# interface_dac_sma_feedback_3PS_LM317.net
KiCad netlist of a schematic drawn in EAGLE
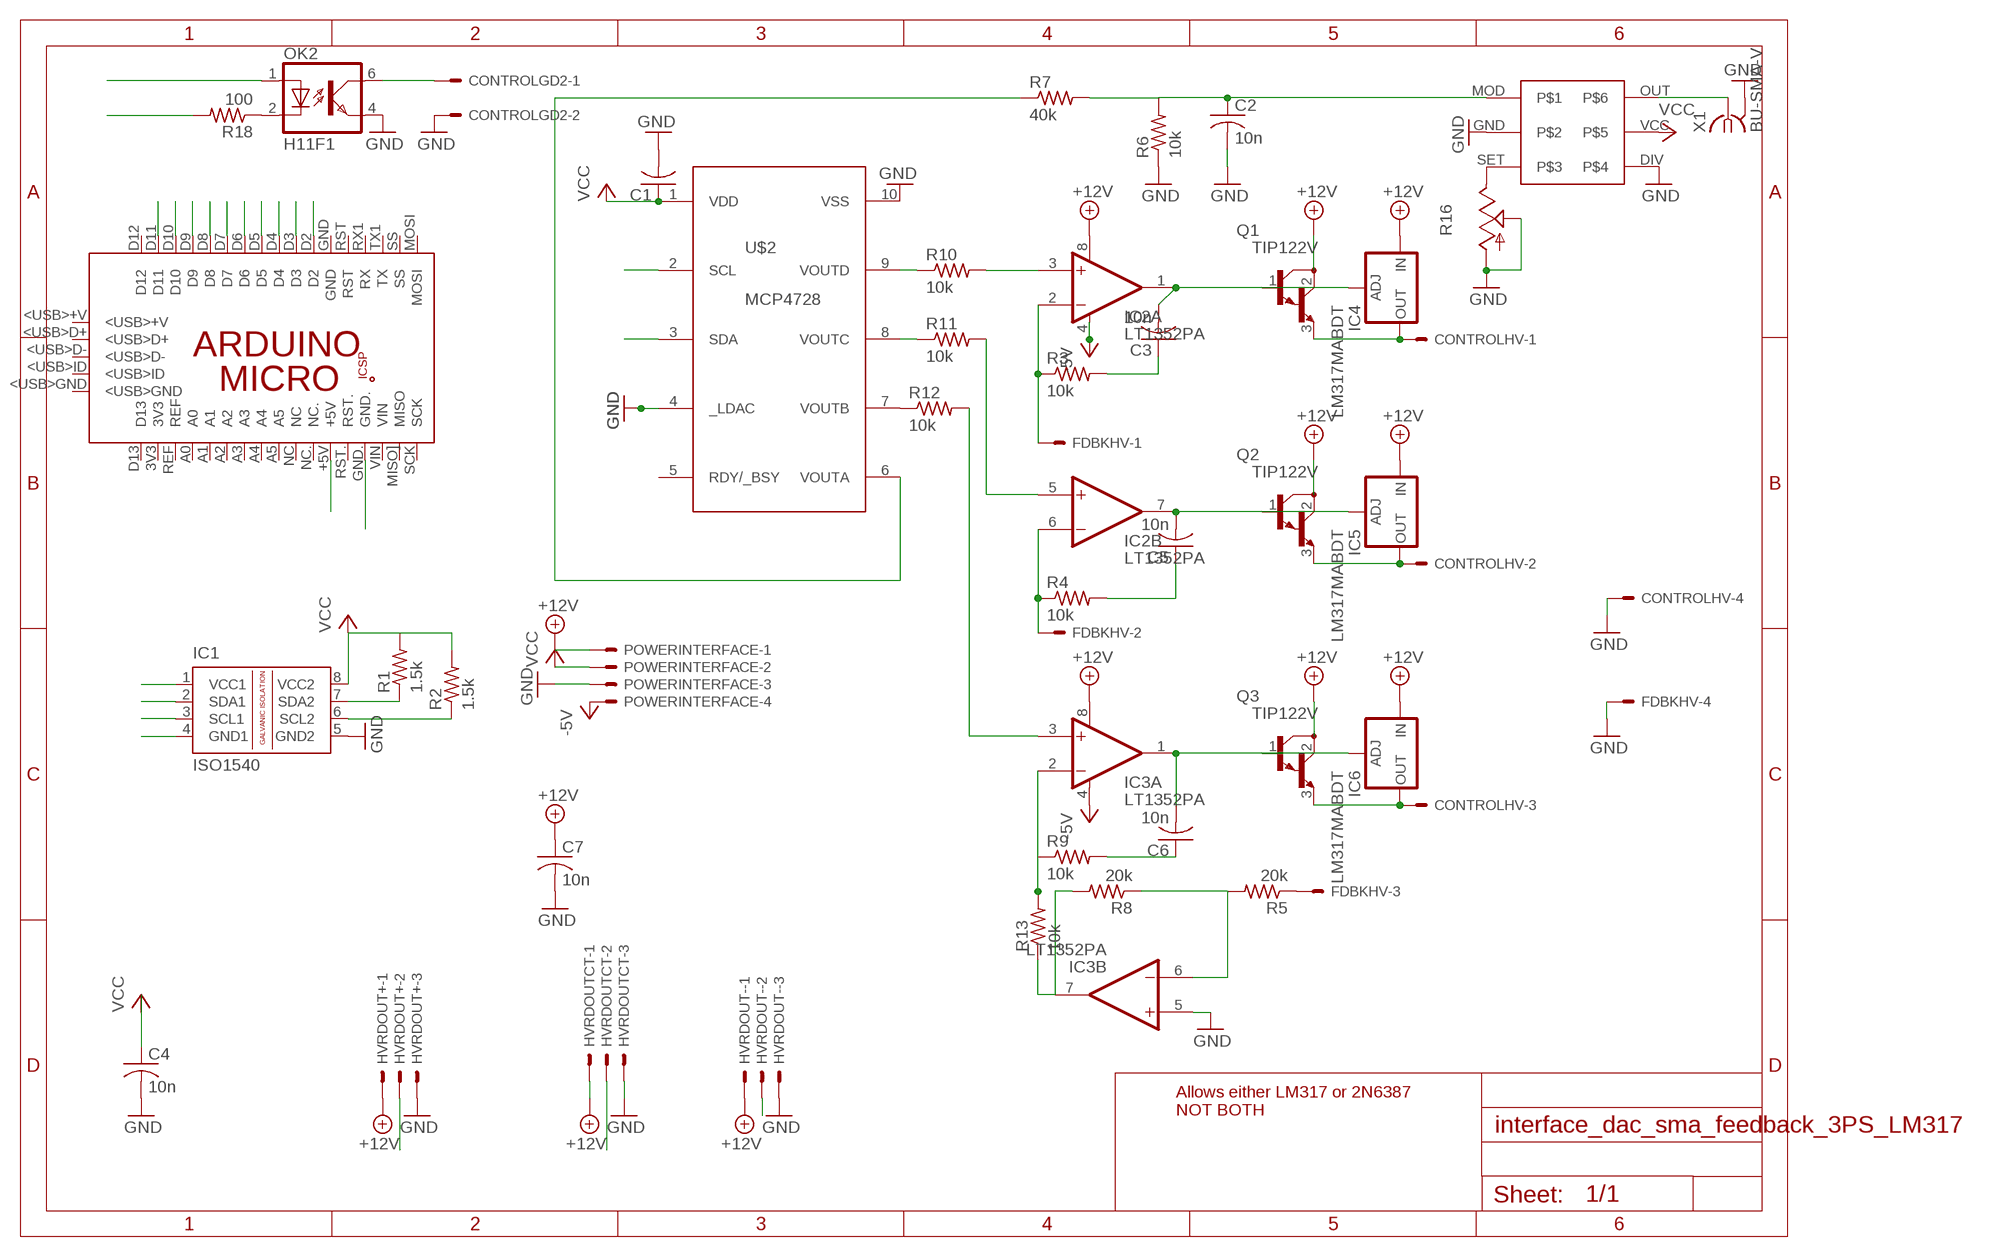
[diagram p0: schematic, sheet 1]

(export (version "E")
  (design (tool "Eeschema 10.0.6"))
  (components
    (comp (ref "C1")
      (value "C-US050-050X075")
      (footprint "eagle-import:C050-050X075")
      (libsource (lib "eagle-import") (part "C-US050-050X075"))
    )
    (comp (ref "C2")
      (value "10n")
      (footprint "eagle-import:C050-024X044")
      (libsource (lib "eagle-import") (part "resistor_C-US050-024X044"))
    )
    (comp (ref "C3")
      (value "10n")
      (footprint "eagle-import:C050-024X044")
      (libsource (lib "eagle-import") (part "resistor_C-US050-024X044"))
    )
    (comp (ref "C4")
      (value "10n")
      (footprint "eagle-import:C075-063X106")
      (libsource (lib "eagle-import") (part "resistor_C-US075-063X106"))
    )
    (comp (ref "C5")
      (value "10n")
      (footprint "eagle-import:C050-024X044")
      (libsource (lib "eagle-import") (part "resistor_C-US050-024X044"))
    )
    (comp (ref "C6")
      (value "10n")
      (footprint "eagle-import:C050-024X044")
      (libsource (lib "eagle-import") (part "resistor_C-US050-024X044"))
    )
    (comp (ref "C7")
      (value "10n")
      (footprint "eagle-import:C050-050X075")
      (libsource (lib "eagle-import") (part "resistor_C-US050-050X075"))
    )
    (comp (ref "CONTROLGD2")
      (value "KK-156-2")
      (footprint "eagle-import:KK-156-2")
      (libsource (lib "eagle-import") (part "KK-156-2"))
    )
    (comp (ref "CONTROLHV")
      (value "KK-156-4")
      (footprint "eagle-import:KK-156-4")
      (libsource (lib "eagle-import") (part "KK-156-4"))
    )
    (comp (ref "FDBKHV")
      (value "KK-156-4")
      (footprint "eagle-import:KK-156-4")
      (libsource (lib "eagle-import") (part "KK-156-4"))
    )
    (comp (ref "HVRDOUT+")
      (value "KK-156-3")
      (footprint "eagle-import:KK-156-3")
      (libsource (lib "eagle-import") (part "KK-156-3"))
    )
    (comp (ref "HVRDOUT-")
      (value "KK-156-3")
      (footprint "eagle-import:KK-156-3")
      (libsource (lib "eagle-import") (part "KK-156-3"))
    )
    (comp (ref "HVRDOUTCT")
      (value "KK-156-3")
      (footprint "eagle-import:KK-156-3")
      (libsource (lib "eagle-import") (part "KK-156-3"))
    )
    (comp (ref "IC1")
      (value "ISO1540")
      (footprint "eagle-import:DIL08")
      (libsource (lib "eagle-import") (part "ISO1540"))
    )
    (comp (ref "IC2")
      (value "LT1352PA")
      (footprint "eagle-import:DIL08")
      (libsource (lib "eagle-import") (part "LT1352PA"))
    )
    (comp (ref "IC3")
      (value "LT1352PA")
      (footprint "eagle-import:DIL08")
      (libsource (lib "eagle-import") (part "LT1352PA"))
    )
    (comp (ref "IC4")
      (value "LM317MABDT")
      (footprint "eagle-import:DPACK")
      (libsource (lib "eagle-import") (part "v-reg_LM317?MABDT"))
    )
    (comp (ref "IC5")
      (value "LM317MABDT")
      (footprint "eagle-import:DPACK")
      (libsource (lib "eagle-import") (part "v-reg_LM317?MABDT"))
    )
    (comp (ref "IC6")
      (value "LM317MABDT")
      (footprint "eagle-import:DPACK")
      (libsource (lib "eagle-import") (part "v-reg_LM317?MABDT"))
    )
    (comp (ref "OK2")
      (value "H11F1")
      (footprint "eagle-import:DIL05")
      (libsource (lib "eagle-import") (part "H11F1"))
    )
    (comp (ref "PCB1")
      (value "ARDUINO_MICRO")
      (footprint "eagle-import:ARDUINO_MICRO")
      (libsource (lib "eagle-import") (part "ARDUINO_MICRO"))
    )
    (comp (ref "POWERINTERFACE")
      (value "KK-156-4")
      (footprint "eagle-import:KK-156-4")
      (libsource (lib "eagle-import") (part "KK-156-4"))
    )
    (comp (ref "Q1")
      (value "TIP122V")
      (footprint "eagle-import:TO220V")
      (libsource (lib "eagle-import") (part "TIP122V"))
    )
    (comp (ref "Q2")
      (value "TIP122V")
      (footprint "eagle-import:TO220V")
      (libsource (lib "eagle-import") (part "TIP122V"))
    )
    (comp (ref "Q3")
      (value "TIP122V")
      (footprint "eagle-import:TO220V")
      (libsource (lib "eagle-import") (part "TIP122V"))
    )
    (comp (ref "R1")
      (value "1.5k")
      (footprint "eagle-import:0207_12")
      (libsource (lib "eagle-import") (part "resistor_R-US_0207/12"))
    )
    (comp (ref "R2")
      (value "1.5k")
      (footprint "eagle-import:0207_12")
      (libsource (lib "eagle-import") (part "resistor_R-US_0207/12"))
    )
    (comp (ref "R3")
      (value "10k")
      (footprint "eagle-import:0207_12")
      (libsource (lib "eagle-import") (part "resistor_R-US_0207/12"))
    )
    (comp (ref "R4")
      (value "10k")
      (footprint "eagle-import:0207_12")
      (libsource (lib "eagle-import") (part "resistor_R-US_0207/12"))
    )
    (comp (ref "R5")
      (value "20k")
      (footprint "eagle-import:0207_12")
      (libsource (lib "eagle-import") (part "resistor_R-US_0207/12"))
    )
    (comp (ref "R6")
      (value "10k")
      (footprint "eagle-import:0207_12")
      (libsource (lib "eagle-import") (part "resistor_R-US_0207/12"))
    )
    (comp (ref "R7")
      (value "40k")
      (footprint "eagle-import:0207_12")
      (libsource (lib "eagle-import") (part "resistor_R-US_0207/12"))
    )
    (comp (ref "R8")
      (value "20k")
      (footprint "eagle-import:0207_12")
      (libsource (lib "eagle-import") (part "resistor_R-US_0207/12"))
    )
    (comp (ref "R9")
      (value "10k")
      (footprint "eagle-import:0207_12")
      (libsource (lib "eagle-import") (part "resistor_R-US_0207/12"))
    )
    (comp (ref "R10")
      (value "10k")
      (footprint "eagle-import:0207_12")
      (libsource (lib "eagle-import") (part "resistor_R-US_0207/12"))
    )
    (comp (ref "R11")
      (value "10k")
      (footprint "eagle-import:0207_12")
      (libsource (lib "eagle-import") (part "resistor_R-US_0207/12"))
    )
    (comp (ref "R12")
      (value "10k")
      (footprint "eagle-import:0207_12")
      (libsource (lib "eagle-import") (part "resistor_R-US_0207/12"))
    )
    (comp (ref "R13")
      (value "10k")
      (footprint "eagle-import:0207_12")
      (libsource (lib "eagle-import") (part "resistor_R-US_0207/12"))
    )
    (comp (ref "R16")
      (value "TRIM_US-B90P")
      (footprint "eagle-import:SP19L")
      (libsource (lib "eagle-import") (part "TRIM_US-B90P"))
    )
    (comp (ref "R18")
      (value "100")
      (footprint "eagle-import:0207_12")
      (libsource (lib "eagle-import") (part "R-US_0207/12"))
    )
    (comp (ref "U$1")
      (value "LTC6992")
      (footprint "eagle-import:DIL06")
      (libsource (lib "eagle-import") (part "LTC6992"))
    )
    (comp (ref "U$2")
      (value "MCP4728DIL")
      (footprint "eagle-import:DIL10")
      (libsource (lib "eagle-import") (part "MCP4728DIL"))
    )
    (comp (ref "X1")
      (value "BU-SMA-V")
      (footprint "eagle-import:BU-SMA-V")
      (libsource (lib "eagle-import") (part "BU-SMA-V"))
    )
  )
  (nets
    (net (code "1") (name "+12V") (class "Default")
      (node (ref "C7") (pin "1") (pinfunction "1_1") (pintype "passive"))
      (node (ref "HVRDOUT+") (pin "1") (pinfunction "S_1") (pintype "passive"))
      (node (ref "HVRDOUT-") (pin "1") (pinfunction "S_1") (pintype "passive"))
      (node (ref "HVRDOUTCT") (pin "1") (pinfunction "S_1") (pintype "passive"))
      (node (ref "IC2") (pin "8") (pinfunction "V+_8") (pintype "power_in"))
      (node (ref "IC3") (pin "8") (pinfunction "V+_8") (pintype "power_in"))
      (node (ref "IC4") (pin "3") (pinfunction "IN_3") (pintype "input"))
      (node (ref "IC5") (pin "3") (pinfunction "IN_3") (pintype "input"))
      (node (ref "IC6") (pin "3") (pinfunction "IN_3") (pintype "input"))
      (node (ref "POWERINTERFACE") (pin "1") (pinfunction "S_1") (pintype "passive"))
      (node (ref "Q1") (pin "2") (pinfunction "C_2") (pintype "passive"))
      (node (ref "Q2") (pin "2") (pinfunction "C_2") (pintype "passive"))
      (node (ref "Q3") (pin "2") (pinfunction "C_2") (pintype "passive"))
    )
    (net (code "2") (name "-5V") (class "Default")
      (node (ref "IC2") (pin "4") (pinfunction "V-_4") (pintype "power_in"))
      (node (ref "IC3") (pin "4") (pinfunction "V-_4") (pintype "power_in"))
      (node (ref "POWERINTERFACE") (pin "4") (pinfunction "S_4") (pintype "passive"))
    )
    (net (code "3") (name "/A+5") (class "Default")
      (node (ref "IC1") (pin "1") (pinfunction "VCC1_1") (pintype "input"))
      (node (ref "PCB1") (pin "+5V") (pinfunction "+5V_+5V") (pintype "bidirectional"))
    )
    (net (code "4") (name "/AGND") (class "Default")
      (node (ref "IC1") (pin "4") (pinfunction "GND1_4") (pintype "input"))
      (node (ref "PCB1") (pin "GND.") (pinfunction "GND._GND.") (pintype "bidirectional"))
      (node (ref "R18") (pin "2") (pinfunction "2_2") (pintype "passive"))
    )
    (net (code "5") (name "/N$2") (class "Default")
      (node (ref "C2") (pin "1") (pinfunction "1_1") (pintype "passive"))
      (node (ref "R6") (pin "2") (pinfunction "2_2") (pintype "passive"))
      (node (ref "R7") (pin "2") (pinfunction "2_2") (pintype "passive"))
      (node (ref "U$1") (pin "MOD") (pinfunction "P$1_MOD") (pintype "bidirectional"))
    )
    (net (code "6") (name "/N$6") (class "Default")
      (node (ref "FDBKHV") (pin "2") (pinfunction "S_2") (pintype "passive"))
      (node (ref "HVRDOUTCT") (pin "2") (pinfunction "S_2") (pintype "passive"))
      (node (ref "IC2") (pin "6") (pinfunction "-IN_6") (pintype "input"))
      (node (ref "R4") (pin "1") (pinfunction "1_1") (pintype "passive"))
    )
    (net (code "7") (name "/N$8") (class "Default")
      (node (ref "FDBKHV") (pin "1") (pinfunction "S_1") (pintype "passive"))
      (node (ref "HVRDOUT+") (pin "2") (pinfunction "S_2") (pintype "passive"))
      (node (ref "IC2") (pin "2") (pinfunction "-IN_2") (pintype "input"))
      (node (ref "R3") (pin "1") (pinfunction "1_1") (pintype "passive"))
    )
    (net (code "8") (name "/N$14") (class "Default")
      (node (ref "HVRDOUT-") (pin "2") (pinfunction "S_2") (pintype "passive"))
      (node (ref "IC3") (pin "7") (pinfunction "OUT_7") (pintype "output"))
      (node (ref "R13") (pin "1") (pinfunction "1_1") (pintype "passive"))
      (node (ref "R8") (pin "2") (pinfunction "2_2") (pintype "passive"))
    )
    (net (code "9") (name "/PWM9") (class "Default")
      (node (ref "OK2") (pin "1") (pinfunction "A_1") (pintype "passive"))
      (node (ref "PCB1") (pin "D9") (pinfunction "D9_D9") (pintype "bidirectional"))
    )
    (net (code "10") (name "/SCL") (class "Default")
      (node (ref "IC1") (pin "3") (pinfunction "SCL1_3") (pintype "input"))
      (node (ref "PCB1") (pin "D3") (pinfunction "D3_D3") (pintype "bidirectional"))
    )
    (net (code "11") (name "/SCL_OUT") (class "Default")
      (node (ref "IC1") (pin "6") (pinfunction "SCL2_6") (pintype "input"))
      (node (ref "R2") (pin "1") (pinfunction "1_1") (pintype "passive"))
      (node (ref "U$2") (pin "2") (pinfunction "SCL_2") (pintype "bidirectional"))
    )
    (net (code "12") (name "/SDA") (class "Default")
      (node (ref "IC1") (pin "2") (pinfunction "SDA1_2") (pintype "input"))
      (node (ref "PCB1") (pin "D2") (pinfunction "D2_D2") (pintype "bidirectional"))
    )
    (net (code "13") (name "/SDA_OUT") (class "Default")
      (node (ref "IC1") (pin "7") (pinfunction "SDA2_7") (pintype "input"))
      (node (ref "R1") (pin "1") (pinfunction "1_1") (pintype "passive"))
      (node (ref "U$2") (pin "3") (pinfunction "SDA_3") (pintype "bidirectional"))
    )
    (net (code "14") (name "GND") (class "Default")
      (node (ref "C1") (pin "2") (pinfunction "2_2") (pintype "passive"))
      (node (ref "C2") (pin "2") (pinfunction "2_2") (pintype "passive"))
      (node (ref "C4") (pin "2") (pinfunction "2_2") (pintype "passive"))
      (node (ref "C7") (pin "2") (pinfunction "2_2") (pintype "passive"))
      (node (ref "CONTROLGD2") (pin "2") (pinfunction "S_2") (pintype "passive"))
      (node (ref "CONTROLHV") (pin "4") (pinfunction "S_4") (pintype "passive"))
      (node (ref "FDBKHV") (pin "4") (pinfunction "S_4") (pintype "passive"))
      (node (ref "HVRDOUT+") (pin "3") (pinfunction "S_3") (pintype "passive"))
      (node (ref "HVRDOUT-") (pin "3") (pinfunction "S_3") (pintype "passive"))
      (node (ref "HVRDOUTCT") (pin "3") (pinfunction "S_3") (pintype "passive"))
      (node (ref "IC1") (pin "5") (pinfunction "GND2_5") (pintype "input"))
      (node (ref "IC3") (pin "5") (pinfunction "+IN_5") (pintype "input"))
      (node (ref "OK2") (pin "4") (pinfunction "EMIT_4") (pintype "passive"))
      (node (ref "POWERINTERFACE") (pin "3") (pinfunction "S_3") (pintype "passive"))
      (node (ref "R16") (pin "A") (pinfunction "A_A") (pintype "passive"))
      (node (ref "R16") (pin "S") (pinfunction "S_S") (pintype "passive"))
      (node (ref "R6") (pin "1") (pinfunction "1_1") (pintype "passive"))
      (node (ref "U$1") (pin "DIV") (pinfunction "P$4_DIV") (pintype "bidirectional"))
      (node (ref "U$1") (pin "GND") (pinfunction "P$2_GND") (pintype "bidirectional"))
      (node (ref "U$2") (pin "10") (pinfunction "VSS_10") (pintype "bidirectional"))
      (node (ref "U$2") (pin "4") (pinfunction "_LDAC_4") (pintype "bidirectional"))
      (node (ref "X1") (pin "2") (pinfunction "2_2") (pintype "passive"))
      (node (ref "X1") (pin "3") (pinfunction "2_3") (pintype "passive"))
      (node (ref "X1") (pin "4") (pinfunction "2_4") (pintype "passive"))
      (node (ref "X1") (pin "5") (pinfunction "2_5") (pintype "passive"))
    )
    (net (code "15") (name "Net-(C3-Pad1)") (class "Default")
      (node (ref "C3") (pin "1") (pinfunction "1_1") (pintype "passive"))
      (node (ref "R3") (pin "2") (pinfunction "2_2") (pintype "passive"))
    )
    (net (code "16") (name "Net-(C5-Pad1)") (class "Default")
      (node (ref "C5") (pin "1") (pinfunction "1_1") (pintype "passive"))
      (node (ref "R4") (pin "2") (pinfunction "2_2") (pintype "passive"))
    )
    (net (code "17") (name "Net-(C6-Pad1)") (class "Default")
      (node (ref "C6") (pin "1") (pinfunction "1_1") (pintype "passive"))
      (node (ref "R9") (pin "2") (pinfunction "2_2") (pintype "passive"))
    )
    (net (code "18") (name "Net-(CONTROLGD2A-S)") (class "Default")
      (node (ref "CONTROLGD2") (pin "1") (pinfunction "S_1") (pintype "passive"))
      (node (ref "OK2") (pin "6") (pinfunction "COL_6") (pintype "passive"))
    )
    (net (code "19") (name "Net-(CONTROLHVA-S)") (class "Default")
      (node (ref "CONTROLHV") (pin "1") (pinfunction "S_1") (pintype "passive"))
      (node (ref "IC4") (pin "4") (pinfunction "OUT_4") (pintype "passive"))
      (node (ref "Q1") (pin "3") (pinfunction "E_3") (pintype "passive"))
    )
    (net (code "20") (name "Net-(CONTROLHVB-S)") (class "Default")
      (node (ref "CONTROLHV") (pin "2") (pinfunction "S_2") (pintype "passive"))
      (node (ref "IC5") (pin "4") (pinfunction "OUT_4") (pintype "passive"))
      (node (ref "Q2") (pin "3") (pinfunction "E_3") (pintype "passive"))
    )
    (net (code "21") (name "Net-(CONTROLHVC-S)") (class "Default")
      (node (ref "CONTROLHV") (pin "3") (pinfunction "S_3") (pintype "passive"))
      (node (ref "IC6") (pin "4") (pinfunction "OUT_4") (pintype "passive"))
      (node (ref "Q3") (pin "3") (pinfunction "E_3") (pintype "passive"))
    )
    (net (code "22") (name "Net-(FDBKHVC-S)") (class "Default")
      (node (ref "FDBKHV") (pin "3") (pinfunction "S_3") (pintype "passive"))
      (node (ref "R5") (pin "1") (pinfunction "1_1") (pintype "passive"))
    )
    (net (code "23") (name "Net-(IC2A-+IN)") (class "Default")
      (node (ref "IC2") (pin "3") (pinfunction "+IN_3") (pintype "input"))
      (node (ref "R10") (pin "2") (pinfunction "2_2") (pintype "passive"))
    )
    (net (code "24") (name "Net-(IC2A-OUT)") (class "Default")
      (node (ref "C3") (pin "2") (pinfunction "2_2") (pintype "passive"))
      (node (ref "IC2") (pin "1") (pinfunction "OUT_1") (pintype "output"))
      (node (ref "IC4") (pin "1") (pinfunction "ADJ_1") (pintype "input"))
      (node (ref "Q1") (pin "1") (pinfunction "B_1") (pintype "passive"))
    )
    (net (code "25") (name "Net-(IC2B-+IN)") (class "Default")
      (node (ref "IC2") (pin "5") (pinfunction "+IN_5") (pintype "input"))
      (node (ref "R11") (pin "2") (pinfunction "2_2") (pintype "passive"))
    )
    (net (code "26") (name "Net-(IC2B-OUT)") (class "Default")
      (node (ref "C5") (pin "2") (pinfunction "2_2") (pintype "passive"))
      (node (ref "IC2") (pin "7") (pinfunction "OUT_7") (pintype "output"))
      (node (ref "IC5") (pin "1") (pinfunction "ADJ_1") (pintype "input"))
      (node (ref "Q2") (pin "1") (pinfunction "B_1") (pintype "passive"))
    )
    (net (code "27") (name "Net-(IC3A-+IN)") (class "Default")
      (node (ref "IC3") (pin "3") (pinfunction "+IN_3") (pintype "input"))
      (node (ref "R12") (pin "2") (pinfunction "2_2") (pintype "passive"))
    )
    (net (code "28") (name "Net-(IC3A--IN)") (class "Default")
      (node (ref "IC3") (pin "2") (pinfunction "-IN_2") (pintype "input"))
      (node (ref "R13") (pin "2") (pinfunction "2_2") (pintype "passive"))
      (node (ref "R9") (pin "1") (pinfunction "1_1") (pintype "passive"))
    )
    (net (code "29") (name "Net-(IC3A-OUT)") (class "Default")
      (node (ref "C6") (pin "2") (pinfunction "2_2") (pintype "passive"))
      (node (ref "IC3") (pin "1") (pinfunction "OUT_1") (pintype "output"))
      (node (ref "IC6") (pin "1") (pinfunction "ADJ_1") (pintype "input"))
      (node (ref "Q3") (pin "1") (pinfunction "B_1") (pintype "passive"))
    )
    (net (code "30") (name "Net-(IC3B--IN)") (class "Default")
      (node (ref "IC3") (pin "6") (pinfunction "-IN_6") (pintype "input"))
      (node (ref "R5") (pin "2") (pinfunction "2_2") (pintype "passive"))
      (node (ref "R8") (pin "1") (pinfunction "1_1") (pintype "passive"))
    )
    (net (code "31") (name "Net-(OK2-C)") (class "Default")
      (node (ref "OK2") (pin "2") (pinfunction "C_2") (pintype "passive"))
      (node (ref "R18") (pin "1") (pinfunction "1_1") (pintype "passive"))
    )
    (net (code "32") (name "Net-(U$1-P$3)") (class "Default")
      (node (ref "R16") (pin "E") (pinfunction "E_E") (pintype "passive"))
      (node (ref "U$1") (pin "SET") (pinfunction "P$3_SET") (pintype "bidirectional"))
    )
    (net (code "33") (name "Net-(U$1-P$6)") (class "Default")
      (node (ref "U$1") (pin "OUT") (pinfunction "P$6_OUT") (pintype "bidirectional"))
      (node (ref "X1") (pin "1") (pinfunction "1_1") (pintype "passive"))
    )
    (net (code "34") (name "Net-(U$2-VOUTA)") (class "Default")
      (node (ref "R7") (pin "1") (pinfunction "1_1") (pintype "passive"))
      (node (ref "U$2") (pin "6") (pinfunction "VOUTA_6") (pintype "bidirectional"))
    )
    (net (code "35") (name "Net-(U$2-VOUTB)") (class "Default")
      (node (ref "R12") (pin "1") (pinfunction "1_1") (pintype "passive"))
      (node (ref "U$2") (pin "7") (pinfunction "VOUTB_7") (pintype "bidirectional"))
    )
    (net (code "36") (name "Net-(U$2-VOUTC)") (class "Default")
      (node (ref "R11") (pin "1") (pinfunction "1_1") (pintype "passive"))
      (node (ref "U$2") (pin "8") (pinfunction "VOUTC_8") (pintype "bidirectional"))
    )
    (net (code "37") (name "Net-(U$2-VOUTD)") (class "Default")
      (node (ref "R10") (pin "1") (pinfunction "1_1") (pintype "passive"))
      (node (ref "U$2") (pin "9") (pinfunction "VOUTD_9") (pintype "bidirectional"))
    )
    (net (code "38") (name "VCC") (class "Default")
      (node (ref "C1") (pin "1") (pinfunction "1_1") (pintype "passive"))
      (node (ref "C4") (pin "1") (pinfunction "1_1") (pintype "passive"))
      (node (ref "IC1") (pin "8") (pinfunction "VCC2_8") (pintype "input"))
      (node (ref "POWERINTERFACE") (pin "2") (pinfunction "S_2") (pintype "passive"))
      (node (ref "R1") (pin "2") (pinfunction "2_2") (pintype "passive"))
      (node (ref "R2") (pin "2") (pinfunction "2_2") (pintype "passive"))
      (node (ref "U$1") (pin "VCC") (pinfunction "P$5_VCC") (pintype "bidirectional"))
      (node (ref "U$2") (pin "1") (pinfunction "VDD_1") (pintype "bidirectional"))
    )
    (net (code "39") (name "unconnected-(PCB1-MISO-PadMISO])") (class "Default")
      (node (ref "PCB1") (pin "MISO]") (pinfunction "MISO_MISO]") (pintype "bidirectional"))
    )
    (net (code "40") (name "unconnected-(PCB1-Pad3V3)") (class "Default")
      (node (ref "PCB1") (pin "3V3") (pinfunction "3V3_3V3") (pintype "bidirectional"))
    )
    (net (code "41") (name "unconnected-(PCB1-Pad5V)") (class "Default")
      (node (ref "PCB1") (pin "5V") (pinfunction "5V_5V") (pintype "bidirectional"))
    )
    (net (code "42") (name "unconnected-(PCB1-Pad<USB>+V)") (class "Default")
      (node (ref "PCB1") (pin "<USB>+V") (pinfunction "<USB>+V_<USB>+V") (pintype "bidirectional"))
    )
    (net (code "43") (name "unconnected-(PCB1-Pad<USB>D+)") (class "Default")
      (node (ref "PCB1") (pin "<USB>D+") (pinfunction "<USB>D+_<USB>D+") (pintype "bidirectional"))
    )
    (net (code "44") (name "unconnected-(PCB1-Pad<USB>D-)") (class "Default")
      (node (ref "PCB1") (pin "<USB>D-") (pinfunction "<USB>D-_<USB>D-") (pintype "bidirectional"))
    )
    (net (code "45") (name "unconnected-(PCB1-Pad<USB>GND)") (class "Default")
      (node (ref "PCB1") (pin "<USB>GND") (pinfunction "<USB>GND_<USB>GND") (pintype "bidirectional"))
    )
    (net (code "46") (name "unconnected-(PCB1-Pad<USB>ID)") (class "Default")
      (node (ref "PCB1") (pin "<USB>ID") (pinfunction "<USB>ID_<USB>ID") (pintype "bidirectional"))
    )
    (net (code "47") (name "unconnected-(PCB1-PadA0)") (class "Default")
      (node (ref "PCB1") (pin "A0") (pinfunction "A0_A0") (pintype "bidirectional"))
    )
    (net (code "48") (name "unconnected-(PCB1-PadA1)") (class "Default")
      (node (ref "PCB1") (pin "A1") (pinfunction "A1_A1") (pintype "bidirectional"))
    )
    (net (code "49") (name "unconnected-(PCB1-PadA2)") (class "Default")
      (node (ref "PCB1") (pin "A2") (pinfunction "A2_A2") (pintype "bidirectional"))
    )
    (net (code "50") (name "unconnected-(PCB1-PadA3)") (class "Default")
      (node (ref "PCB1") (pin "A3") (pinfunction "A3_A3") (pintype "bidirectional"))
    )
    (net (code "51") (name "unconnected-(PCB1-PadA4)") (class "Default")
      (node (ref "PCB1") (pin "A4") (pinfunction "A4_A4") (pintype "bidirectional"))
    )
    (net (code "52") (name "unconnected-(PCB1-PadA5)") (class "Default")
      (node (ref "PCB1") (pin "A5") (pinfunction "A5_A5") (pintype "bidirectional"))
    )
    (net (code "53") (name "unconnected-(PCB1-PadD4)") (class "Default")
      (node (ref "PCB1") (pin "D4") (pinfunction "D4_D4") (pintype "bidirectional"))
    )
    (net (code "54") (name "unconnected-(PCB1-PadD5)") (class "Default")
      (node (ref "PCB1") (pin "D5") (pinfunction "D5_D5") (pintype "bidirectional"))
    )
    (net (code "55") (name "unconnected-(PCB1-PadD6)") (class "Default")
      (node (ref "PCB1") (pin "D6") (pinfunction "D6_D6") (pintype "bidirectional"))
    )
    (net (code "56") (name "unconnected-(PCB1-PadD7)") (class "Default")
      (node (ref "PCB1") (pin "D7") (pinfunction "D7_D7") (pintype "bidirectional"))
    )
    (net (code "57") (name "unconnected-(PCB1-PadD8)") (class "Default")
      (node (ref "PCB1") (pin "D8") (pinfunction "D8_D8") (pintype "bidirectional"))
    )
    (net (code "58") (name "unconnected-(PCB1-PadD10)") (class "Default")
      (node (ref "PCB1") (pin "D10") (pinfunction "D10_D10") (pintype "bidirectional"))
    )
    (net (code "59") (name "unconnected-(PCB1-PadD11)") (class "Default")
      (node (ref "PCB1") (pin "D11") (pinfunction "D11_D11") (pintype "bidirectional"))
    )
    (net (code "60") (name "unconnected-(PCB1-PadD12)") (class "Default")
      (node (ref "PCB1") (pin "D12") (pinfunction "D12_D12") (pintype "bidirectional"))
    )
    (net (code "61") (name "unconnected-(PCB1-PadD13)") (class "Default")
      (node (ref "PCB1") (pin "D13") (pinfunction "D13_D13") (pintype "bidirectional"))
    )
    (net (code "62") (name "unconnected-(PCB1-PadGND)") (class "Default")
      (node (ref "PCB1") (pin "GND") (pinfunction "GND_GND") (pintype "bidirectional"))
    )
    (net (code "63") (name "unconnected-(PCB1-PadGND_)") (class "Default")
      (node (ref "PCB1") (pin "GND_") (pinfunction "GND__GND_") (pintype "bidirectional"))
    )
    (net (code "64") (name "unconnected-(PCB1-PadMISO.)") (class "Default")
      (node (ref "PCB1") (pin "MISO.") (pinfunction "MISO._MISO.") (pintype "bidirectional"))
    )
    (net (code "65") (name "unconnected-(PCB1-PadMOSI)") (class "Default")
      (node (ref "PCB1") (pin "MOSI") (pinfunction "MOSI_MOSI") (pintype "bidirectional"))
    )
    (net (code "66") (name "unconnected-(PCB1-PadMOSI.)") (class "Default")
      (node (ref "PCB1") (pin "MOSI.") (pinfunction "MOSI._MOSI.") (pintype "bidirectional"))
    )
    (net (code "67") (name "unconnected-(PCB1-PadNC)") (class "Default")
      (node (ref "PCB1") (pin "NC") (pinfunction "NC_NC") (pintype "bidirectional"))
    )
    (net (code "68") (name "unconnected-(PCB1-PadNC.)") (class "Default")
      (node (ref "PCB1") (pin "NC.") (pinfunction "NC._NC.") (pintype "bidirectional"))
    )
    (net (code "69") (name "unconnected-(PCB1-PadREF)") (class "Default")
      (node (ref "PCB1") (pin "REF") (pinfunction "REF_REF") (pintype "bidirectional"))
    )
    (net (code "70") (name "unconnected-(PCB1-PadRESET..)") (class "Default")
      (node (ref "PCB1") (pin "RESET..") (pinfunction "RESET.._RESET..") (pintype "bidirectional"))
    )
    (net (code "71") (name "unconnected-(PCB1-PadRST)") (class "Default")
      (node (ref "PCB1") (pin "RST") (pinfunction "RST_RST") (pintype "bidirectional"))
    )
    (net (code "72") (name "unconnected-(PCB1-PadRST.)") (class "Default")
      (node (ref "PCB1") (pin "RST.") (pinfunction "RST._RST.") (pintype "bidirectional"))
    )
    (net (code "73") (name "unconnected-(PCB1-PadSCK)") (class "Default")
      (node (ref "PCB1") (pin "SCK") (pinfunction "SCK_SCK") (pintype "bidirectional"))
    )
    (net (code "74") (name "unconnected-(PCB1-PadSCK.)") (class "Default")
      (node (ref "PCB1") (pin "SCK.") (pinfunction "SCK._SCK.") (pintype "bidirectional"))
    )
    (net (code "75") (name "unconnected-(PCB1-PadSS)") (class "Default")
      (node (ref "PCB1") (pin "SS") (pinfunction "SS_SS") (pintype "bidirectional"))
    )
    (net (code "76") (name "unconnected-(PCB1-PadVIN)") (class "Default")
      (node (ref "PCB1") (pin "VIN") (pinfunction "VIN_VIN") (pintype "bidirectional"))
    )
    (net (code "77") (name "unconnected-(PCB1-RX-PadRX1)") (class "Default")
      (node (ref "PCB1") (pin "RX1") (pinfunction "RX_RX1") (pintype "bidirectional"))
    )
    (net (code "78") (name "unconnected-(PCB1-TX-PadTX1)") (class "Default")
      (node (ref "PCB1") (pin "TX1") (pinfunction "TX_TX1") (pintype "bidirectional"))
    )
    (net (code "79") (name "unconnected-(U$2-RDY{slash}_BSY-Pad5)") (class "Default")
      (node (ref "U$2") (pin "5") (pinfunction "RDY/_BSY_5") (pintype "bidirectional"))
    )
  )
)
